# GOMSIS.net
KiCad netlist of a schematic drawn in Altium Designer
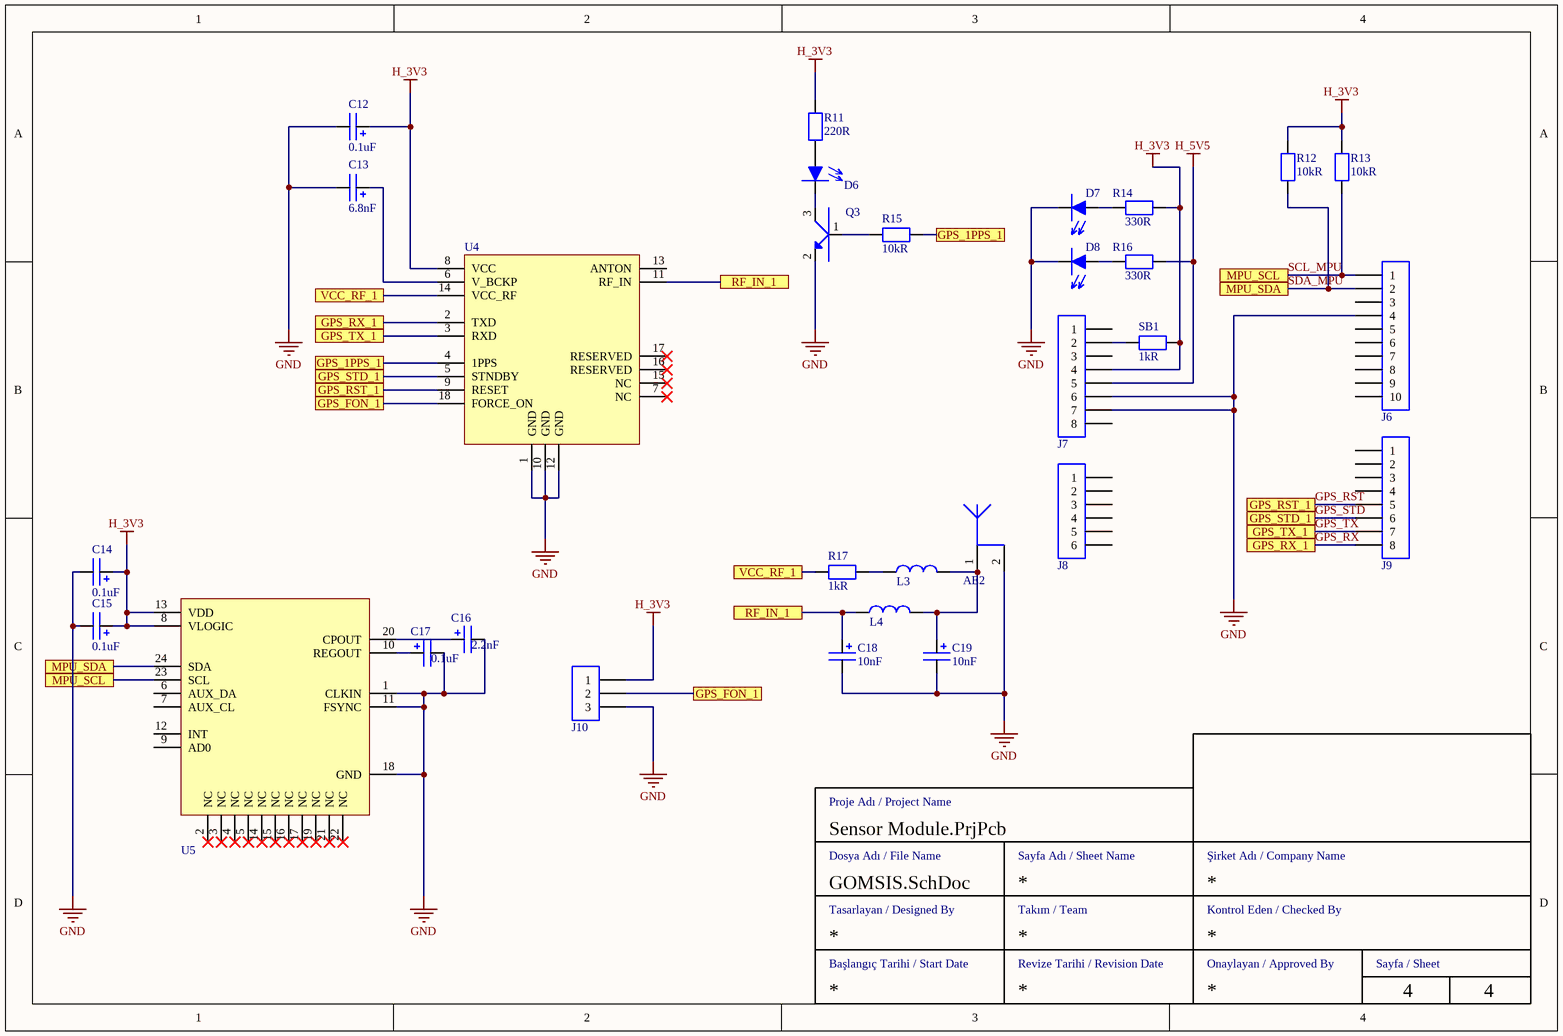
[diagram p0: GOMSIS.SchDoc]

(export (version "E")
  (design (tool "Eeschema 10.0.6"))
  (components
    (comp (ref "AE2")
      (value "UFL Connector")
      (footprint "UFL CONN")
      (description "Antenna Connector")
      (libsource (lib "Kaptanyums Lib") (part "UFL Connector"))
    )
    (comp (ref "C12")
      (value "0.1uF")
      (footprint "CAP 0603")
      (description "Multilayer Ceramic Capacitor")
      (fields (field (name "Comment") "CAP 0603"))
      (libsource (lib "Kaptanyums Lib") (part "CAP 0603"))
    )
    (comp (ref "C13")
      (value "6.8nF")
      (footprint "CAP 0603")
      (description "Multilayer Ceramic Capacitor")
      (fields (field (name "Comment") "CAP 0603"))
      (libsource (lib "Kaptanyums Lib") (part "CAP 0603"))
    )
    (comp (ref "C14")
      (value "0.1uF")
      (footprint "CAP 0603")
      (description "Multilayer Ceramic Capacitor")
      (fields (field (name "Comment") "CAP 0603"))
      (libsource (lib "Kaptanyums Lib") (part "CAP 0603"))
    )
    (comp (ref "C15")
      (value "0.1uF")
      (footprint "CAP 0603")
      (description "Multilayer Ceramic Capacitor")
      (fields (field (name "Comment") "CAP 0603"))
      (libsource (lib "Kaptanyums Lib") (part "CAP 0603"))
    )
    (comp (ref "C16")
      (value "2.2nF")
      (footprint "CAP 0603")
      (description "Multilayer Ceramic Capacitor")
      (fields (field (name "Comment") "CAP 0603"))
      (libsource (lib "Kaptanyums Lib") (part "CAP 0603"))
    )
    (comp (ref "C17")
      (value "0.1uF")
      (footprint "CAP 0603")
      (description "Multilayer Ceramic Capacitor")
      (fields (field (name "Comment") "CAP 0603"))
      (libsource (lib "Kaptanyums Lib") (part "CAP 0603"))
    )
    (comp (ref "C18")
      (value "10nF")
      (footprint "CAP 0603")
      (description "Multilayer Ceramic Capacitor")
      (fields (field (name "Comment") "CAP 0603"))
      (libsource (lib "Kaptanyums Lib") (part "CAP 0603"))
    )
    (comp (ref "C19")
      (value "10nF")
      (footprint "CAP 0603")
      (description "Multilayer Ceramic Capacitor")
      (fields (field (name "Comment") "CAP 0603"))
      (libsource (lib "Kaptanyums Lib") (part "CAP 0603"))
    )
    (comp (ref "D6")
      (value "LTW-C191TLA")
      (footprint "LED 0603")
      (description "Chip LED")
      (libsource (lib "Kaptanyums Lib") (part "LED 0603"))
    )
    (comp (ref "D7")
      (value "LTW-C191TLA")
      (footprint "LED 0603")
      (description "Chip LED")
      (libsource (lib "Kaptanyums Lib") (part "LED 0603"))
    )
    (comp (ref "D8")
      (value "LTW-C191TLA")
      (footprint "LED 0603")
      (description "Chip LED")
      (libsource (lib "Kaptanyums Lib") (part "LED 0603"))
    )
    (comp (ref "J6")
      (value "HMATHT00C101")
      (footprint "HMATHT00C101")
      (description "Header for PCB")
      (libsource (lib "Kaptanyums Lib") (part "HMATHT00C101"))
    )
    (comp (ref "J7")
      (value "HMATHT00C81")
      (footprint "HMATHT00C81 - duplicate")
      (description "Header for PCB")
      (libsource (lib "Schlib") (part "HMATHT00C81"))
    )
    (comp (ref "J8")
      (value "5-146285-6")
      (footprint "HMATHT00C61")
      (description "Header for PCB")
      (libsource (lib "Kaptanyums Lib") (part "HMATHT00C61"))
    )
    (comp (ref "J9")
      (value "HMATHT00C81")
      (footprint "HMATHT00C81 - duplicate")
      (description "Header for PCB")
      (libsource (lib "Schlib") (part "HMATHT00C81"))
    )
    (comp (ref "J10")
      (value "146285-3")
      (footprint "HMATHT00C31")
      (description "Header for PCB")
      (libsource (lib "Kaptanyums Lib") (part "HMATHT00C31"))
    )
    (comp (ref "L3")
      (value "IND 0603")
      (footprint "INDUCTOR 0603")
      (description "SMD Inductor")
      (libsource (lib "Schlib") (part "IND 0603"))
    )
    (comp (ref "L4")
      (value "IND 0603")
      (footprint "INDUCTOR 0603")
      (description "SMD Inductor")
      (libsource (lib "Schlib") (part "IND 0603"))
    )
    (comp (ref "Q3")
      (value "BC817-40")
      (footprint "SOT23-3")
      (description "Transistor BJT")
      (fields (field (name "VOLTAGE") "45V"))
      (libsource (lib "Kaptanyums Lib") (part "BC817-40"))
    )
    (comp (ref "R11")
      (value "220R")
      (footprint "RESISTOR 0603")
      (description "SMD Chip Resistor")
      (fields (field (name "Comment") "RES 0603"))
      (libsource (lib "Kaptanyums Lib") (part "RES 0603"))
    )
    (comp (ref "R12")
      (value "10kR")
      (footprint "RESISTOR 0603")
      (description "SMD Chip Resistor")
      (fields (field (name "Comment") "RES 0603"))
      (libsource (lib "Kaptanyums Lib") (part "RES 0603"))
    )
    (comp (ref "R13")
      (value "10kR")
      (footprint "RESISTOR 0603")
      (description "SMD Chip Resistor")
      (fields (field (name "Comment") "RES 0603"))
      (libsource (lib "Kaptanyums Lib") (part "RES 0603"))
    )
    (comp (ref "R14")
      (value "330R")
      (footprint "RESISTOR 0603")
      (description "SMD Chip Resistor")
      (fields (field (name "Comment") "RES 0603"))
      (libsource (lib "Kaptanyums Lib") (part "RES 0603"))
    )
    (comp (ref "R15")
      (value "10kR")
      (footprint "RESISTOR 0603")
      (description "SMD Chip Resistor")
      (fields (field (name "Comment") "RES 0603"))
      (libsource (lib "Kaptanyums Lib") (part "RES 0603"))
    )
    (comp (ref "R16")
      (value "330R")
      (footprint "RESISTOR 0603")
      (description "SMD Chip Resistor")
      (fields (field (name "Comment") "RES 0603"))
      (libsource (lib "Kaptanyums Lib") (part "RES 0603"))
    )
    (comp (ref "R17")
      (value "1kR")
      (footprint "RESISTOR 0603")
      (description "SMD Chip Resistor")
      (fields (field (name "Comment") "RES 0603"))
      (libsource (lib "Kaptanyums Lib") (part "RES 0603"))
    )
    (comp (ref "SB1")
      (value "1kR")
      (footprint "RESISTOR 0603")
      (description "SMD Chip Resistor")
      (fields (field (name "Comment") "RES 0603"))
      (libsource (lib "Kaptanyums Lib") (part "RES 0603"))
    )
    (comp (ref "U4")
      (value "L76M33")
      (footprint "L76M33")
      (description "GPS, GLONASS, GNSS Transceiver")
      (libsource (lib "Kaptanyums Lib") (part "L76M33"))
    )
    (comp (ref "U5")
      (value "MPU6050")
      (footprint "QFN24")
      (description "IMU")
      (libsource (lib "Schlib") (part "MPU6050"))
    )
  )
  (nets
    (net (code "1") (name "/GPS_1PPS_1") (class "Default")
      (node (ref "R15") (pin "2") (pinfunction "2_2") (pintype "passive"))
      (node (ref "U4") (pin "4") (pinfunction "1PPS_4") (pintype "passive"))
    )
    (net (code "2") (name "/GPS_FON_1") (class "Default")
      (node (ref "J10") (pin "2") (pinfunction "2_2") (pintype "passive"))
      (node (ref "U4") (pin "18") (pinfunction "FORCE_ON_18") (pintype "passive"))
    )
    (net (code "3") (name "/GPS_RST") (class "Default")
      (node (ref "J9") (pin "5") (pinfunction "5_5") (pintype "passive"))
      (node (ref "U4") (pin "9") (pinfunction "RESET_9") (pintype "passive"))
    )
    (net (code "4") (name "/GPS_RX") (class "Default")
      (node (ref "J9") (pin "8") (pinfunction "8_8") (pintype "passive"))
      (node (ref "U4") (pin "2") (pinfunction "TXD_2") (pintype "passive"))
    )
    (net (code "5") (name "/GPS_STD") (class "Default")
      (node (ref "J9") (pin "6") (pinfunction "6_6") (pintype "passive"))
      (node (ref "U4") (pin "5") (pinfunction "STNDBY_5") (pintype "passive"))
    )
    (net (code "6") (name "/GPS_TX") (class "Default")
      (node (ref "J9") (pin "7") (pinfunction "7_7") (pintype "passive"))
      (node (ref "U4") (pin "3") (pinfunction "RXD_3") (pintype "passive"))
    )
    (net (code "7") (name "/RF_IN_1") (class "Default")
      (node (ref "C18") (pin "1") (pinfunction "1_1") (pintype "passive"))
      (node (ref "L4") (pin "1") (pinfunction "1_1") (pintype "passive"))
      (node (ref "U4") (pin "11") (pinfunction "RF_IN_11") (pintype "passive"))
    )
    (net (code "8") (name "/SCL_MPU") (class "Default")
      (node (ref "J6") (pin "1") (pinfunction "1_1") (pintype "passive"))
      (node (ref "R13") (pin "1") (pinfunction "1_1") (pintype "passive"))
      (node (ref "U5") (pin "23") (pinfunction "SCL_23") (pintype "passive"))
    )
    (net (code "9") (name "/SDA_MPU") (class "Default")
      (node (ref "J6") (pin "2") (pinfunction "2_2") (pintype "passive"))
      (node (ref "R12") (pin "1") (pinfunction "1_1") (pintype "passive"))
      (node (ref "U5") (pin "24") (pinfunction "SDA_24") (pintype "passive"))
    )
    (net (code "10") (name "/VCC_RF_1") (class "Default")
      (node (ref "R17") (pin "1") (pinfunction "1_1") (pintype "passive"))
      (node (ref "U4") (pin "14") (pinfunction "VCC_RF_14") (pintype "passive"))
    )
    (net (code "11") (name "GND") (class "Default")
      (node (ref "AE2") (pin "2") (pinfunction "2_2") (pintype "passive"))
      (node (ref "C12") (pin "2") (pinfunction "2_2") (pintype "passive"))
      (node (ref "C13") (pin "2") (pinfunction "2_2") (pintype "passive"))
      (node (ref "C14") (pin "2") (pinfunction "2_2") (pintype "passive"))
      (node (ref "C15") (pin "2") (pinfunction "2_2") (pintype "passive"))
      (node (ref "C16") (pin "2") (pinfunction "2_2") (pintype "passive"))
      (node (ref "C17") (pin "2") (pinfunction "2_2") (pintype "passive"))
      (node (ref "C18") (pin "2") (pinfunction "2_2") (pintype "passive"))
      (node (ref "C19") (pin "2") (pinfunction "2_2") (pintype "passive"))
      (node (ref "D7") (pin "1") (pinfunction "1_1") (pintype "passive"))
      (node (ref "D8") (pin "1") (pinfunction "1_1") (pintype "passive"))
      (node (ref "J10") (pin "3") (pinfunction "3_3") (pintype "passive"))
      (node (ref "J6") (pin "4") (pinfunction "4_4") (pintype "passive"))
      (node (ref "J7") (pin "6") (pinfunction "6_6") (pintype "passive"))
      (node (ref "J7") (pin "7") (pinfunction "7_7") (pintype "passive"))
      (node (ref "Q3") (pin "2") (pinfunction "S_2") (pintype "passive"))
      (node (ref "U4") (pin "1") (pinfunction "GND_1") (pintype "passive"))
      (node (ref "U4") (pin "10") (pinfunction "GND_10") (pintype "passive"))
      (node (ref "U4") (pin "12") (pinfunction "GND_12") (pintype "passive"))
      (node (ref "U5") (pin "1") (pinfunction "CLKIN_1") (pintype "passive"))
      (node (ref "U5") (pin "11") (pinfunction "FSYNC_11") (pintype "passive"))
      (node (ref "U5") (pin "18") (pinfunction "GND_18") (pintype "passive"))
    )
    (net (code "12") (name "H_3V3") (class "Default")
      (node (ref "C12") (pin "1") (pinfunction "1_1") (pintype "passive"))
      (node (ref "C14") (pin "1") (pinfunction "1_1") (pintype "passive"))
      (node (ref "C15") (pin "1") (pinfunction "1_1") (pintype "passive"))
      (node (ref "J10") (pin "1") (pinfunction "1_1") (pintype "passive"))
      (node (ref "J7") (pin "4") (pinfunction "4_4") (pintype "passive"))
      (node (ref "R11") (pin "2") (pinfunction "2_2") (pintype "passive"))
      (node (ref "R12") (pin "2") (pinfunction "2_2") (pintype "passive"))
      (node (ref "R13") (pin "2") (pinfunction "2_2") (pintype "passive"))
      (node (ref "R14") (pin "1") (pinfunction "1_1") (pintype "passive"))
      (node (ref "SB1") (pin "1") (pinfunction "1_1") (pintype "passive"))
      (node (ref "U4") (pin "8") (pinfunction "VCC_8") (pintype "passive"))
      (node (ref "U5") (pin "13") (pinfunction "VDD_13") (pintype "passive"))
      (node (ref "U5") (pin "8") (pinfunction "VLOGIC_8") (pintype "passive"))
    )
    (net (code "13") (name "H_5V5") (class "Default")
      (node (ref "J7") (pin "5") (pinfunction "5_5") (pintype "passive"))
      (node (ref "R16") (pin "1") (pinfunction "1_1") (pintype "passive"))
    )
    (net (code "14") (name "Net-(AE2-Pad1)") (class "Default")
      (node (ref "AE2") (pin "1") (pinfunction "1_1") (pintype "passive"))
      (node (ref "C19") (pin "1") (pinfunction "1_1") (pintype "passive"))
      (node (ref "L3") (pin "2") (pinfunction "2_2") (pintype "passive"))
      (node (ref "L4") (pin "2") (pinfunction "2_2") (pintype "passive"))
    )
    (net (code "15") (name "Net-(D6-Pad2)") (class "Default")
      (node (ref "D6") (pin "2") (pinfunction "2_2") (pintype "passive"))
      (node (ref "R11") (pin "1") (pinfunction "1_1") (pintype "passive"))
    )
    (net (code "16") (name "Net-(D7-Pad2)") (class "Default")
      (node (ref "D7") (pin "2") (pinfunction "2_2") (pintype "passive"))
      (node (ref "R14") (pin "2") (pinfunction "2_2") (pintype "passive"))
    )
    (net (code "17") (name "Net-(D8-Pad2)") (class "Default")
      (node (ref "D8") (pin "2") (pinfunction "2_2") (pintype "passive"))
      (node (ref "R16") (pin "2") (pinfunction "2_2") (pintype "passive"))
    )
    (net (code "18") (name "Net-(J7-Pad2)") (class "Default")
      (node (ref "J7") (pin "2") (pinfunction "2_2") (pintype "passive"))
      (node (ref "SB1") (pin "2") (pinfunction "2_2") (pintype "passive"))
    )
    (net (code "19") (name "Net-(L3-Pad1)") (class "Default")
      (node (ref "L3") (pin "1") (pinfunction "1_1") (pintype "passive"))
      (node (ref "R17") (pin "2") (pinfunction "2_2") (pintype "passive"))
    )
    (net (code "20") (name "Net-(Q3-D)") (class "Default")
      (node (ref "D6") (pin "1") (pinfunction "1_1") (pintype "passive"))
      (node (ref "Q3") (pin "3") (pinfunction "D_3") (pintype "passive"))
    )
    (net (code "21") (name "Net-(Q3-G)") (class "Default")
      (node (ref "Q3") (pin "1") (pinfunction "G_1") (pintype "passive"))
      (node (ref "R15") (pin "1") (pinfunction "1_1") (pintype "passive"))
    )
    (net (code "22") (name "Net-(U4-V_BCKP)") (class "Default")
      (node (ref "C13") (pin "1") (pinfunction "1_1") (pintype "passive"))
      (node (ref "U4") (pin "6") (pinfunction "V_BCKP_6") (pintype "passive"))
    )
    (net (code "23") (name "Net-(U5-CPOUT)") (class "Default")
      (node (ref "C16") (pin "1") (pinfunction "1_1") (pintype "passive"))
      (node (ref "U5") (pin "20") (pinfunction "CPOUT_20") (pintype "passive"))
    )
    (net (code "24") (name "Net-(U5-REGOUT)") (class "Default")
      (node (ref "C17") (pin "1") (pinfunction "1_1") (pintype "passive"))
      (node (ref "U5") (pin "10") (pinfunction "REGOUT_10") (pintype "passive"))
    )
    (net (code "25") (name "unconnected-(J6-Pad3)") (class "Default")
      (node (ref "J6") (pin "3") (pinfunction "3_3") (pintype "passive"))
    )
    (net (code "26") (name "unconnected-(J6-Pad5)") (class "Default")
      (node (ref "J6") (pin "5") (pinfunction "5_5") (pintype "passive"))
    )
    (net (code "27") (name "unconnected-(J6-Pad6)") (class "Default")
      (node (ref "J6") (pin "6") (pinfunction "6_6") (pintype "passive"))
    )
    (net (code "28") (name "unconnected-(J6-Pad7)") (class "Default")
      (node (ref "J6") (pin "7") (pinfunction "7_7") (pintype "passive"))
    )
    (net (code "29") (name "unconnected-(J6-Pad8)") (class "Default")
      (node (ref "J6") (pin "8") (pinfunction "8_8") (pintype "passive"))
    )
    (net (code "30") (name "unconnected-(J6-Pad9)") (class "Default")
      (node (ref "J6") (pin "9") (pinfunction "9_9") (pintype "passive"))
    )
    (net (code "31") (name "unconnected-(J6-Pad10)") (class "Default")
      (node (ref "J6") (pin "10") (pinfunction "10_10") (pintype "passive"))
    )
    (net (code "32") (name "unconnected-(J7-Pad1)") (class "Default")
      (node (ref "J7") (pin "1") (pinfunction "1_1") (pintype "passive"))
    )
    (net (code "33") (name "unconnected-(J7-Pad3)") (class "Default")
      (node (ref "J7") (pin "3") (pinfunction "3_3") (pintype "passive"))
    )
    (net (code "34") (name "unconnected-(J7-Pad8)") (class "Default")
      (node (ref "J7") (pin "8") (pinfunction "8_8") (pintype "passive"))
    )
    (net (code "35") (name "unconnected-(J8-Pad1)") (class "Default")
      (node (ref "J8") (pin "1") (pinfunction "1_1") (pintype "passive"))
    )
    (net (code "36") (name "unconnected-(J8-Pad2)") (class "Default")
      (node (ref "J8") (pin "2") (pinfunction "2_2") (pintype "passive"))
    )
    (net (code "37") (name "unconnected-(J8-Pad3)") (class "Default")
      (node (ref "J8") (pin "3") (pinfunction "3_3") (pintype "passive"))
    )
    (net (code "38") (name "unconnected-(J8-Pad4)") (class "Default")
      (node (ref "J8") (pin "4") (pinfunction "4_4") (pintype "passive"))
    )
    (net (code "39") (name "unconnected-(J8-Pad5)") (class "Default")
      (node (ref "J8") (pin "5") (pinfunction "5_5") (pintype "passive"))
    )
    (net (code "40") (name "unconnected-(J8-Pad6)") (class "Default")
      (node (ref "J8") (pin "6") (pinfunction "6_6") (pintype "passive"))
    )
    (net (code "41") (name "unconnected-(J9-Pad1)") (class "Default")
      (node (ref "J9") (pin "1") (pinfunction "1_1") (pintype "passive"))
    )
    (net (code "42") (name "unconnected-(J9-Pad2)") (class "Default")
      (node (ref "J9") (pin "2") (pinfunction "2_2") (pintype "passive"))
    )
    (net (code "43") (name "unconnected-(J9-Pad3)") (class "Default")
      (node (ref "J9") (pin "3") (pinfunction "3_3") (pintype "passive"))
    )
    (net (code "44") (name "unconnected-(J9-Pad4)") (class "Default")
      (node (ref "J9") (pin "4") (pinfunction "4_4") (pintype "passive"))
    )
    (net (code "45") (name "unconnected-(U4-ANTON-Pad13)") (class "Default")
      (node (ref "U4") (pin "13") (pinfunction "ANTON_13") (pintype "passive"))
    )
    (net (code "46") (name "unconnected-(U4-NC-Pad7)") (class "Default")
      (node (ref "U4") (pin "7") (pinfunction "NC_7") (pintype "passive+no_connect"))
    )
    (net (code "47") (name "unconnected-(U4-NC-Pad15)") (class "Default")
      (node (ref "U4") (pin "15") (pinfunction "NC_15") (pintype "passive+no_connect"))
    )
    (net (code "48") (name "unconnected-(U4-RESERVED-Pad16)") (class "Default")
      (node (ref "U4") (pin "16") (pinfunction "RESERVED_16") (pintype "passive+no_connect"))
    )
    (net (code "49") (name "unconnected-(U4-RESERVED-Pad17)") (class "Default")
      (node (ref "U4") (pin "17") (pinfunction "RESERVED_17") (pintype "passive+no_connect"))
    )
    (net (code "50") (name "unconnected-(U5-AD0-Pad9)") (class "Default")
      (node (ref "U5") (pin "9") (pinfunction "AD0_9") (pintype "passive"))
    )
    (net (code "51") (name "unconnected-(U5-AUX_CL-Pad7)") (class "Default")
      (node (ref "U5") (pin "7") (pinfunction "AUX_CL_7") (pintype "passive"))
    )
    (net (code "52") (name "unconnected-(U5-AUX_DA-Pad6)") (class "Default")
      (node (ref "U5") (pin "6") (pinfunction "AUX_DA_6") (pintype "passive"))
    )
    (net (code "53") (name "unconnected-(U5-INT-Pad12)") (class "Default")
      (node (ref "U5") (pin "12") (pinfunction "INT_12") (pintype "passive"))
    )
    (net (code "54") (name "unconnected-(U5-NC-Pad2)") (class "Default")
      (node (ref "U5") (pin "2") (pinfunction "NC_2") (pintype "passive+no_connect"))
    )
    (net (code "55") (name "unconnected-(U5-NC-Pad3)") (class "Default")
      (node (ref "U5") (pin "3") (pinfunction "NC_3") (pintype "passive+no_connect"))
    )
    (net (code "56") (name "unconnected-(U5-NC-Pad4)") (class "Default")
      (node (ref "U5") (pin "4") (pinfunction "NC_4") (pintype "passive+no_connect"))
    )
    (net (code "57") (name "unconnected-(U5-NC-Pad5)") (class "Default")
      (node (ref "U5") (pin "5") (pinfunction "NC_5") (pintype "passive+no_connect"))
    )
    (net (code "58") (name "unconnected-(U5-NC-Pad14)") (class "Default")
      (node (ref "U5") (pin "14") (pinfunction "NC_14") (pintype "passive+no_connect"))
    )
    (net (code "59") (name "unconnected-(U5-NC-Pad15)") (class "Default")
      (node (ref "U5") (pin "15") (pinfunction "NC_15") (pintype "passive+no_connect"))
    )
    (net (code "60") (name "unconnected-(U5-NC-Pad16)") (class "Default")
      (node (ref "U5") (pin "16") (pinfunction "NC_16") (pintype "passive+no_connect"))
    )
    (net (code "61") (name "unconnected-(U5-NC-Pad17)") (class "Default")
      (node (ref "U5") (pin "17") (pinfunction "NC_17") (pintype "passive+no_connect"))
    )
    (net (code "62") (name "unconnected-(U5-NC-Pad19)") (class "Default")
      (node (ref "U5") (pin "19") (pinfunction "NC_19") (pintype "passive+no_connect"))
    )
    (net (code "63") (name "unconnected-(U5-NC-Pad21)") (class "Default")
      (node (ref "U5") (pin "21") (pinfunction "NC_21") (pintype "passive+no_connect"))
    )
    (net (code "64") (name "unconnected-(U5-NC-Pad22)") (class "Default")
      (node (ref "U5") (pin "22") (pinfunction "NC_22") (pintype "passive+no_connect"))
    )
  )
)
